# PCB_PI3_v0_1.net
KiCad netlist of a schematic drawn in Altium Designer
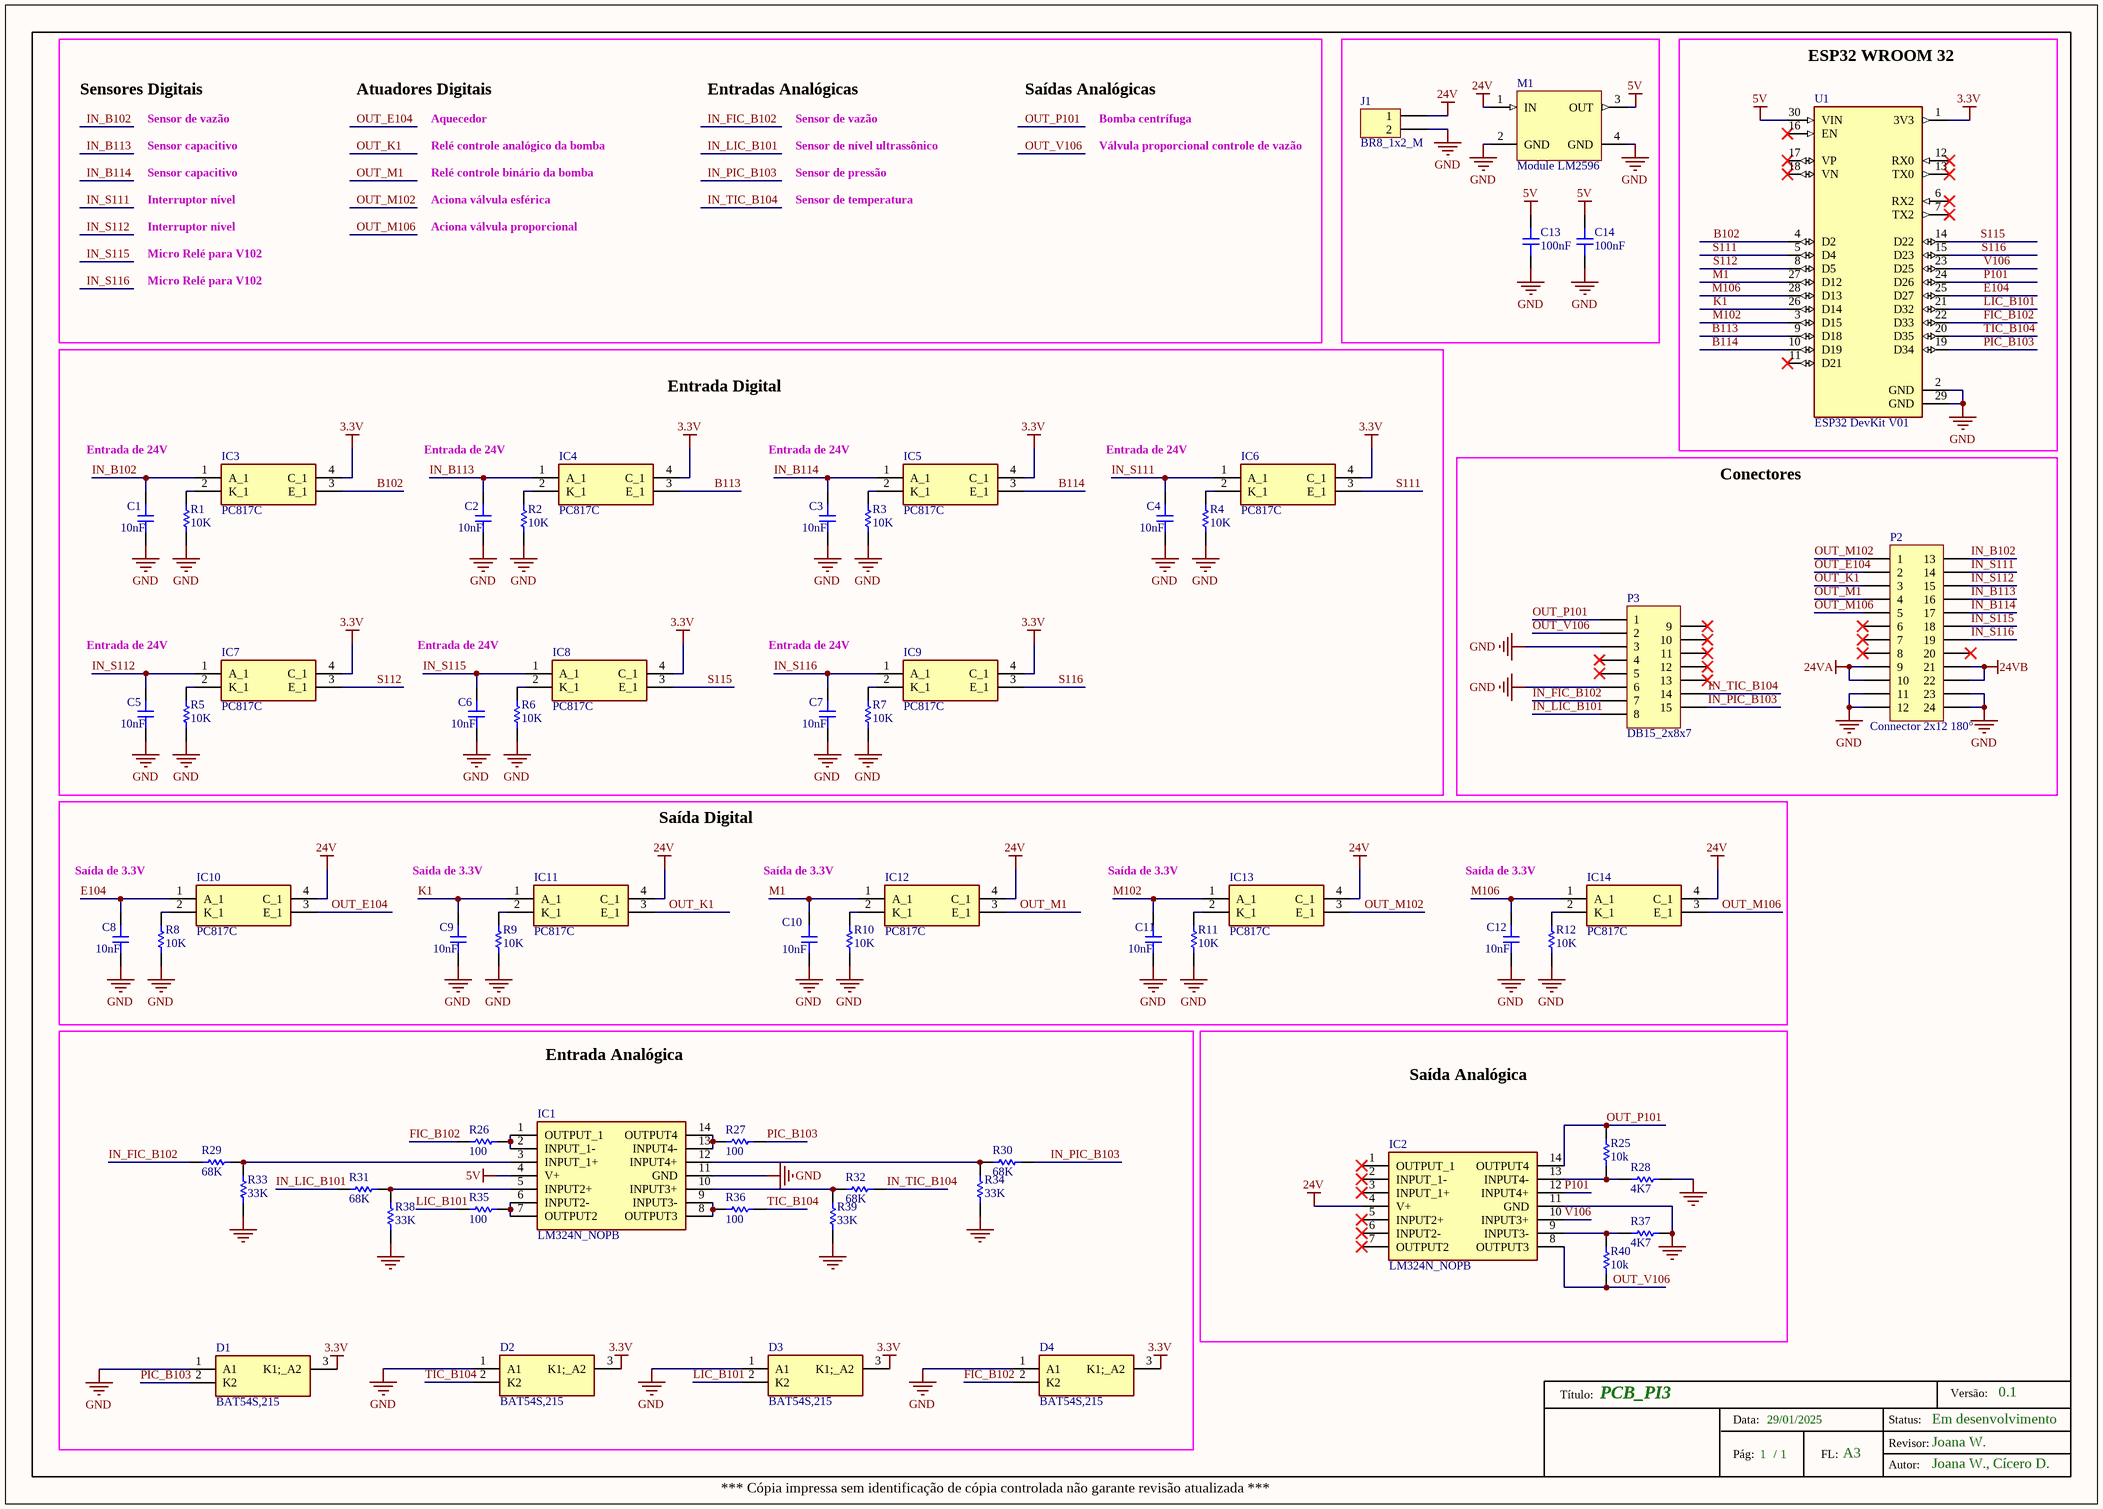
[diagram p0: PCB_PI3_v0.1.SchDoc]

(export (version "E")
  (design (tool "Eeschema 10.0.6"))
  (components
    (comp (ref "C1")
      (value "10nF")
      (footprint "0805C")
      (description "CAP CER 10nF 50V X7R 0805")
      (fields (field (name "VOLTAGE") "50V") (field (name "JLCPCB_PART") "C1710"))
      (libsource (lib "Discrete") (part "C_10nF_0805"))
    )
    (comp (ref "C2")
      (value "10nF")
      (footprint "0805C")
      (description "CAP CER 10nF 50V X7R 0805")
      (fields (field (name "VOLTAGE") "50V") (field (name "JLCPCB_PART") "C1710"))
      (libsource (lib "Discrete") (part "C_10nF_0805"))
    )
    (comp (ref "C3")
      (value "10nF")
      (footprint "0805C")
      (description "CAP CER 10nF 50V X7R 0805")
      (fields (field (name "VOLTAGE") "50V") (field (name "JLCPCB_PART") "C1710"))
      (libsource (lib "Discrete") (part "C_10nF_0805"))
    )
    (comp (ref "C4")
      (value "10nF")
      (footprint "0805C")
      (description "CAP CER 10nF 50V X7R 0805")
      (fields (field (name "VOLTAGE") "50V") (field (name "JLCPCB_PART") "C1710"))
      (libsource (lib "Discrete") (part "C_10nF_0805"))
    )
    (comp (ref "C5")
      (value "10nF")
      (footprint "0805C")
      (description "CAP CER 10nF 50V X7R 0805")
      (fields (field (name "VOLTAGE") "50V") (field (name "JLCPCB_PART") "C1710"))
      (libsource (lib "Discrete") (part "C_10nF_0805"))
    )
    (comp (ref "C6")
      (value "10nF")
      (footprint "0805C")
      (description "CAP CER 10nF 50V X7R 0805")
      (fields (field (name "VOLTAGE") "50V") (field (name "JLCPCB_PART") "C1710"))
      (libsource (lib "Discrete") (part "C_10nF_0805"))
    )
    (comp (ref "C7")
      (value "10nF")
      (footprint "0805C")
      (description "CAP CER 10nF 50V X7R 0805")
      (fields (field (name "VOLTAGE") "50V") (field (name "JLCPCB_PART") "C1710"))
      (libsource (lib "Discrete") (part "C_10nF_0805"))
    )
    (comp (ref "C8")
      (value "10nF")
      (footprint "0805C")
      (description "CAP CER 10nF 50V X7R 0805")
      (fields (field (name "VOLTAGE") "50V") (field (name "JLCPCB_PART") "C1710"))
      (libsource (lib "Discrete") (part "C_10nF_0805"))
    )
    (comp (ref "C9")
      (value "10nF")
      (footprint "0805C")
      (description "CAP CER 10nF 50V X7R 0805")
      (fields (field (name "VOLTAGE") "50V") (field (name "JLCPCB_PART") "C1710"))
      (libsource (lib "Discrete") (part "C_10nF_0805"))
    )
    (comp (ref "C10")
      (value "10nF")
      (footprint "0805C")
      (description "CAP CER 10nF 50V X7R 0805")
      (fields (field (name "VOLTAGE") "50V") (field (name "JLCPCB_PART") "C1710"))
      (libsource (lib "Discrete") (part "C_10nF_0805"))
    )
    (comp (ref "C11")
      (value "10nF")
      (footprint "0805C")
      (description "CAP CER 10nF 50V X7R 0805")
      (fields (field (name "VOLTAGE") "50V") (field (name "JLCPCB_PART") "C1710"))
      (libsource (lib "Discrete") (part "C_10nF_0805"))
    )
    (comp (ref "C12")
      (value "10nF")
      (footprint "0805C")
      (description "CAP CER 10nF 50V X7R 0805")
      (fields (field (name "VOLTAGE") "50V") (field (name "JLCPCB_PART") "C1710"))
      (libsource (lib "Discrete") (part "C_10nF_0805"))
    )
    (comp (ref "C13")
      (value "100nF")
      (footprint "0805C")
      (description "CAP CER 100nF 50V X7R 0805")
      (fields (field (name "VOLTAGE") "50V") (field (name "JLCPCB_PART") "C49678"))
      (libsource (lib "Discrete") (part "C_100nF_0805"))
    )
    (comp (ref "C14")
      (value "100nF")
      (footprint "0805C")
      (description "CAP CER 100nF 50V X7R 0805")
      (fields (field (name "VOLTAGE") "50V") (field (name "JLCPCB_PART") "C49678"))
      (libsource (lib "Discrete") (part "C_100nF_0805"))
    )
    (comp (ref "D1")
      (value "BAT54S,215")
      (footprint "SamacSys:SOT95P230X110-3N")
      (description "Schottky Diode")
      (fields (field (name "MOUSER PART NUMBER") "771-BAT54S-T/R"))
      (libsource (lib "*") (part "BAT54S,215"))
    )
    (comp (ref "D2")
      (value "BAT54S,215")
      (footprint "SamacSys:SOT95P230X110-3N")
      (description "Schottky Diode")
      (fields (field (name "MOUSER PART NUMBER") "771-BAT54S-T/R"))
      (libsource (lib "*") (part "BAT54S,215"))
    )
    (comp (ref "D3")
      (value "BAT54S,215")
      (footprint "SamacSys:SOT95P230X110-3N")
      (description "Schottky Diode")
      (fields (field (name "MOUSER PART NUMBER") "771-BAT54S-T/R"))
      (libsource (lib "*") (part "BAT54S,215"))
    )
    (comp (ref "D4")
      (value "BAT54S,215")
      (footprint "SamacSys:SOT95P230X110-3N")
      (description "Schottky Diode")
      (fields (field (name "MOUSER PART NUMBER") "771-BAT54S-T/R"))
      (libsource (lib "*") (part "BAT54S,215"))
    )
    (comp (ref "IC1")
      (value "LM324N_NOPB")
      (footprint "SamacSys:DIP794W56P254L1905H533Q14N")
      (description "Integrated Circuit")
      (fields
        (field (name "MANUFACTURER_PART_NUMBER") "LM324N/NOPB")
        (field (name "MOUSER PART NUMBER") "926-LM324N/NOPB")
      )
      (libsource (lib "*") (part "LM324N_NOPB"))
    )
    (comp (ref "IC2")
      (value "LM324N_NOPB")
      (footprint "SamacSys:DIP794W56P254L1905H533Q14N")
      (description "Integrated Circuit")
      (fields
        (field (name "MANUFACTURER_PART_NUMBER") "LM324N/NOPB")
        (field (name "MOUSER PART NUMBER") "926-LM324N/NOPB")
      )
      (libsource (lib "*") (part "LM324N_NOPB"))
    )
    (comp (ref "IC3")
      (value "PC817C")
      (footprint "SamacSys:DIP762W60P254L458H450Q4N")
      (description "Integrated Circuit")
      (libsource (lib "SamacSys") (part "PC817C"))
    )
    (comp (ref "IC4")
      (value "PC817C")
      (footprint "SamacSys:DIP762W60P254L458H450Q4N")
      (description "Integrated Circuit")
      (libsource (lib "SamacSys") (part "PC817C"))
    )
    (comp (ref "IC5")
      (value "PC817C")
      (footprint "SamacSys:DIP762W60P254L458H450Q4N")
      (description "Integrated Circuit")
      (libsource (lib "SamacSys") (part "PC817C"))
    )
    (comp (ref "IC6")
      (value "PC817C")
      (footprint "SamacSys:DIP762W60P254L458H450Q4N")
      (description "Integrated Circuit")
      (libsource (lib "SamacSys") (part "PC817C"))
    )
    (comp (ref "IC7")
      (value "PC817C")
      (footprint "SamacSys:DIP762W60P254L458H450Q4N")
      (description "Integrated Circuit")
      (libsource (lib "SamacSys") (part "PC817C"))
    )
    (comp (ref "IC8")
      (value "PC817C")
      (footprint "SamacSys:DIP762W60P254L458H450Q4N")
      (description "Integrated Circuit")
      (libsource (lib "SamacSys") (part "PC817C"))
    )
    (comp (ref "IC9")
      (value "PC817C")
      (footprint "SamacSys:DIP762W60P254L458H450Q4N")
      (description "Integrated Circuit")
      (libsource (lib "SamacSys") (part "PC817C"))
    )
    (comp (ref "IC10")
      (value "PC817C")
      (footprint "SamacSys:DIP762W60P254L458H450Q4N")
      (description "Integrated Circuit")
      (libsource (lib "SamacSys") (part "PC817C"))
    )
    (comp (ref "IC11")
      (value "PC817C")
      (footprint "SamacSys:DIP762W60P254L458H450Q4N")
      (description "Integrated Circuit")
      (libsource (lib "SamacSys") (part "PC817C"))
    )
    (comp (ref "IC12")
      (value "PC817C")
      (footprint "SamacSys:DIP762W60P254L458H450Q4N")
      (description "Integrated Circuit")
      (libsource (lib "SamacSys") (part "PC817C"))
    )
    (comp (ref "IC13")
      (value "PC817C")
      (footprint "SamacSys:DIP762W60P254L458H450Q4N")
      (description "Integrated Circuit")
      (libsource (lib "SamacSys") (part "PC817C"))
    )
    (comp (ref "IC14")
      (value "PC817C")
      (footprint "SamacSys:DIP762W60P254L458H450Q4N")
      (description "Integrated Circuit")
      (libsource (lib "SamacSys") (part "PC817C"))
    )
    (comp (ref "J1")
      (value "BR8_1x2_M")
      (footprint "BR8_1X2_M")
      (description "BR8 Metaltex connector, 1x2, male, 180°")
      (fields (field (name "MANUFACTURER_PART") "BR8MC1-02") (field (name "ML_PART") "CPE08001"))
      (libsource (lib "Connector") (part "BR8_1x2_M"))
    )
    (comp (ref "M1")
      (value "Module LM2596")
      (footprint "MOD_LM2596")
      (description "LM2596 4 Pins")
      (libsource (lib "Module") (part "Mod_Header_LM2596"))
    )
    (comp (ref "P2")
      (value "Connector 2x12 180°")
      (footprint "ds1039")
      (description "Connector DS1078 Female, 180°, 2 Lines, 12 Columns, 24 Pins")
      (libsource (lib "Connector") (part "Connector_2x12_F"))
    )
    (comp (ref "P3")
      (value "DB15_2x8x7")
      (footprint "ds1033")
      (description "Connector DB15 female, 180º, 2 Lines, 7e8 Columns, 26 Pins")
      (libsource (lib "Connector") (part "Connector_2x7e8_F"))
    )
    (comp (ref "R1")
      (value "10K")
      (footprint "0805R")
      (description "RES 10K OHM 5% 1/8W 0805")
      (fields (field (name "JLCPCB_PART") "C17414"))
      (libsource (lib "Discrete") (part "R_10K_0805"))
    )
    (comp (ref "R2")
      (value "10K")
      (footprint "0805R")
      (description "RES 10K OHM 5% 1/8W 0805")
      (fields (field (name "JLCPCB_PART") "C17414"))
      (libsource (lib "Discrete") (part "R_10K_0805"))
    )
    (comp (ref "R3")
      (value "10K")
      (footprint "0805R")
      (description "RES 10K OHM 5% 1/8W 0805")
      (fields (field (name "JLCPCB_PART") "C17414"))
      (libsource (lib "Discrete") (part "R_10K_0805"))
    )
    (comp (ref "R4")
      (value "10K")
      (footprint "0805R")
      (description "RES 10K OHM 5% 1/8W 0805")
      (fields (field (name "JLCPCB_PART") "C17414"))
      (libsource (lib "Discrete") (part "R_10K_0805"))
    )
    (comp (ref "R5")
      (value "10K")
      (footprint "0805R")
      (description "RES 10K OHM 5% 1/8W 0805")
      (fields (field (name "JLCPCB_PART") "C17414"))
      (libsource (lib "Discrete") (part "R_10K_0805"))
    )
    (comp (ref "R6")
      (value "10K")
      (footprint "0805R")
      (description "RES 10K OHM 5% 1/8W 0805")
      (fields (field (name "JLCPCB_PART") "C17414"))
      (libsource (lib "Discrete") (part "R_10K_0805"))
    )
    (comp (ref "R7")
      (value "10K")
      (footprint "0805R")
      (description "RES 10K OHM 5% 1/8W 0805")
      (fields (field (name "JLCPCB_PART") "C17414"))
      (libsource (lib "Discrete") (part "R_10K_0805"))
    )
    (comp (ref "R8")
      (value "10K")
      (footprint "0805R")
      (description "RES 10K OHM 5% 1/8W 0805")
      (fields (field (name "JLCPCB_PART") "C17414"))
      (libsource (lib "Discrete") (part "R_10K_0805"))
    )
    (comp (ref "R9")
      (value "10K")
      (footprint "0805R")
      (description "RES 10K OHM 5% 1/8W 0805")
      (fields (field (name "JLCPCB_PART") "C17414"))
      (libsource (lib "Discrete") (part "R_10K_0805"))
    )
    (comp (ref "R10")
      (value "10K")
      (footprint "0805R")
      (description "RES 10K OHM 5% 1/8W 0805")
      (fields (field (name "JLCPCB_PART") "C17414"))
      (libsource (lib "Discrete") (part "R_10K_0805"))
    )
    (comp (ref "R11")
      (value "10K")
      (footprint "0805R")
      (description "RES 10K OHM 5% 1/8W 0805")
      (fields (field (name "JLCPCB_PART") "C17414"))
      (libsource (lib "Discrete") (part "R_10K_0805"))
    )
    (comp (ref "R12")
      (value "10K")
      (footprint "0805R")
      (description "RES 10K OHM 5% 1/8W 0805")
      (fields (field (name "JLCPCB_PART") "C17414"))
      (libsource (lib "Discrete") (part "R_10K_0805"))
    )
    (comp (ref "R25")
      (value "10k")
      (footprint "RESISTOR")
      (description "RES 10k OHM 5% 1/8W")
      (fields (field (name "JLCPCB_PART") "C17513"))
      (libsource (lib "Discrete") (part "R_10k"))
    )
    (comp (ref "R26")
      (value "100")
      (footprint "RESISTOR")
      (description "RES 100 OHM 5% 1/8")
      (libsource (lib "Discrete") (part "R_0R100"))
    )
    (comp (ref "R27")
      (value "100")
      (footprint "RESISTOR")
      (description "RES 100 OHM 5% 1/8")
      (libsource (lib "Discrete") (part "R_0R100"))
    )
    (comp (ref "R28")
      (value "4K7")
      (footprint "RESISTOR")
      (description "RES 4K7 OHM 5% 1/8W")
      (fields (field (name "JLCPCB_PART") "C17513"))
      (libsource (lib "Discrete") (part "R_4K7"))
    )
    (comp (ref "R29")
      (value "68K")
      (footprint "RESISTOR")
      (description "RES 68K OHM 5% 1/8W")
      (fields (field (name "JLCPCB_PART") "C17513"))
      (libsource (lib "Discrete") (part "R_68K"))
    )
    (comp (ref "R30")
      (value "68K")
      (footprint "RESISTOR")
      (description "RES 68K OHM 5% 1/8W")
      (fields (field (name "JLCPCB_PART") "C17513"))
      (libsource (lib "Discrete") (part "R_68K"))
    )
    (comp (ref "R31")
      (value "68K")
      (footprint "RESISTOR")
      (description "RES 68K OHM 5% 1/8W")
      (fields (field (name "JLCPCB_PART") "C17513"))
      (libsource (lib "Discrete") (part "R_68K"))
    )
    (comp (ref "R32")
      (value "68K")
      (footprint "RESISTOR")
      (description "RES 68K OHM 5% 1/8W")
      (fields (field (name "JLCPCB_PART") "C17513"))
      (libsource (lib "Discrete") (part "R_68K"))
    )
    (comp (ref "R33")
      (value "33K")
      (footprint "RESISTOR")
      (description "RES 33K OHM 5% 1/8W")
      (fields (field (name "JLCPCB_PART") "C17513"))
      (libsource (lib "Discrete") (part "R_33K"))
    )
    (comp (ref "R34")
      (value "33K")
      (footprint "RESISTOR")
      (description "RES 33K OHM 5% 1/8W")
      (fields (field (name "JLCPCB_PART") "C17513"))
      (libsource (lib "Discrete") (part "R_33K"))
    )
    (comp (ref "R35")
      (value "100")
      (footprint "RESISTOR")
      (description "RES 100 OHM 5% 1/8")
      (libsource (lib "Discrete") (part "R_0R100"))
    )
    (comp (ref "R36")
      (value "100")
      (footprint "RESISTOR")
      (description "RES 100 OHM 5% 1/8")
      (libsource (lib "Discrete") (part "R_0R100"))
    )
    (comp (ref "R37")
      (value "4K7")
      (footprint "RESISTOR")
      (description "RES 4K7 OHM 5% 1/8W")
      (fields (field (name "JLCPCB_PART") "C17513"))
      (libsource (lib "Discrete") (part "R_4K7"))
    )
    (comp (ref "R38")
      (value "33K")
      (footprint "RESISTOR")
      (description "RES 33K OHM 5% 1/8W")
      (fields (field (name "JLCPCB_PART") "C17513"))
      (libsource (lib "Discrete") (part "R_33K"))
    )
    (comp (ref "R39")
      (value "33K")
      (footprint "RESISTOR")
      (description "RES 33K OHM 5% 1/8W")
      (fields (field (name "JLCPCB_PART") "C17513"))
      (libsource (lib "Discrete") (part "R_33K"))
    )
    (comp (ref "R40")
      (value "10k")
      (footprint "RESISTOR")
      (description "RES 10k OHM 5% 1/8W")
      (fields (field (name "JLCPCB_PART") "C17513"))
      (libsource (lib "Discrete") (part "R_10k"))
    )
    (comp (ref "U1")
      (value "ESP32 DevKit V01")
      (footprint "ESP32-DEVKIT-V1")
      (description "IC MCU 32BIT ESP32 DEVKIT V01")
      (fields
        (field (name "MANUFACTURER_PART_NUMBER") "ESP-32-DEVKIT-V1")
        (field (name "ML_PART") "CPE11011")
      )
      (libsource (lib "Special") (part "ESP32_DEVKIT"))
    )
  )
  (nets
    (net (code "1") (name "/B102") (class "Default")
      (node (ref "IC3") (pin "3") (pinfunction "E_1_3") (pintype "passive"))
      (node (ref "U1") (pin "4") (pinfunction "D2_4") (pintype "bidirectional"))
    )
    (net (code "2") (name "/B113") (class "Default")
      (node (ref "IC4") (pin "3") (pinfunction "E_1_3") (pintype "passive"))
      (node (ref "U1") (pin "9") (pinfunction "D18_9") (pintype "bidirectional"))
    )
    (net (code "3") (name "/B114") (class "Default")
      (node (ref "IC5") (pin "3") (pinfunction "E_1_3") (pintype "passive"))
      (node (ref "U1") (pin "10") (pinfunction "D19_10") (pintype "bidirectional"))
    )
    (net (code "4") (name "/E104") (class "Default")
      (node (ref "C8") (pin "2") (pinfunction "2_2") (pintype "passive"))
      (node (ref "IC10") (pin "1") (pinfunction "A_1_1") (pintype "passive"))
      (node (ref "U1") (pin "25") (pinfunction "D27_25") (pintype "bidirectional"))
    )
    (net (code "5") (name "/FIC_B102") (class "Default")
      (node (ref "D4") (pin "2") (pinfunction "K2_2") (pintype "passive"))
      (node (ref "R26") (pin "2") (pinfunction "2_2") (pintype "passive"))
      (node (ref "U1") (pin "22") (pinfunction "D33_22") (pintype "bidirectional"))
    )
    (net (code "6") (name "/IN_B102") (class "Default")
      (node (ref "C1") (pin "2") (pinfunction "2_2") (pintype "passive"))
      (node (ref "IC3") (pin "1") (pinfunction "A_1_1") (pintype "passive"))
      (node (ref "P2") (pin "13") (pinfunction "13_13") (pintype "passive"))
    )
    (net (code "7") (name "/IN_B113") (class "Default")
      (node (ref "C2") (pin "2") (pinfunction "2_2") (pintype "passive"))
      (node (ref "IC4") (pin "1") (pinfunction "A_1_1") (pintype "passive"))
      (node (ref "P2") (pin "16") (pinfunction "16_16") (pintype "passive"))
    )
    (net (code "8") (name "/IN_B114") (class "Default")
      (node (ref "C3") (pin "2") (pinfunction "2_2") (pintype "passive"))
      (node (ref "IC5") (pin "1") (pinfunction "A_1_1") (pintype "passive"))
      (node (ref "P2") (pin "17") (pinfunction "17_17") (pintype "passive"))
    )
    (net (code "9") (name "/IN_FIC_B102") (class "Default")
      (node (ref "P3") (pin "7") (pinfunction "7_7") (pintype "passive"))
      (node (ref "R29") (pin "2") (pinfunction "2_2") (pintype "passive"))
    )
    (net (code "10") (name "/IN_LIC_B101") (class "Default")
      (node (ref "P3") (pin "8") (pinfunction "8_8") (pintype "passive"))
      (node (ref "R31") (pin "2") (pinfunction "2_2") (pintype "passive"))
    )
    (net (code "11") (name "/IN_PIC_B103") (class "Default")
      (node (ref "P3") (pin "15") (pinfunction "15_15") (pintype "passive"))
      (node (ref "R30") (pin "1") (pinfunction "1_1") (pintype "passive"))
    )
    (net (code "12") (name "/IN_S111") (class "Default")
      (node (ref "C4") (pin "2") (pinfunction "2_2") (pintype "passive"))
      (node (ref "IC6") (pin "1") (pinfunction "A_1_1") (pintype "passive"))
      (node (ref "P2") (pin "14") (pinfunction "14_14") (pintype "passive"))
    )
    (net (code "13") (name "/IN_S112") (class "Default")
      (node (ref "C5") (pin "2") (pinfunction "2_2") (pintype "passive"))
      (node (ref "IC7") (pin "1") (pinfunction "A_1_1") (pintype "passive"))
      (node (ref "P2") (pin "15") (pinfunction "15_15") (pintype "passive"))
    )
    (net (code "14") (name "/IN_S115") (class "Default")
      (node (ref "C6") (pin "2") (pinfunction "2_2") (pintype "passive"))
      (node (ref "IC8") (pin "1") (pinfunction "A_1_1") (pintype "passive"))
      (node (ref "P2") (pin "18") (pinfunction "18_18") (pintype "passive"))
    )
    (net (code "15") (name "/IN_S116") (class "Default")
      (node (ref "C7") (pin "2") (pinfunction "2_2") (pintype "passive"))
      (node (ref "IC9") (pin "1") (pinfunction "A_1_1") (pintype "passive"))
      (node (ref "P2") (pin "19") (pinfunction "19_19") (pintype "passive"))
    )
    (net (code "16") (name "/IN_TIC_B104") (class "Default")
      (node (ref "P3") (pin "14") (pinfunction "14_14") (pintype "passive"))
      (node (ref "R32") (pin "1") (pinfunction "1_1") (pintype "passive"))
    )
    (net (code "17") (name "/K1") (class "Default")
      (node (ref "C9") (pin "2") (pinfunction "2_2") (pintype "passive"))
      (node (ref "IC11") (pin "1") (pinfunction "A_1_1") (pintype "passive"))
      (node (ref "U1") (pin "26") (pinfunction "D14_26") (pintype "bidirectional"))
    )
    (net (code "18") (name "/LIC_B101") (class "Default")
      (node (ref "D3") (pin "2") (pinfunction "K2_2") (pintype "passive"))
      (node (ref "R35") (pin "2") (pinfunction "2_2") (pintype "passive"))
      (node (ref "U1") (pin "21") (pinfunction "D32_21") (pintype "bidirectional"))
    )
    (net (code "19") (name "/M1") (class "Default")
      (node (ref "C10") (pin "2") (pinfunction "2_2") (pintype "passive"))
      (node (ref "IC12") (pin "1") (pinfunction "A_1_1") (pintype "passive"))
      (node (ref "U1") (pin "27") (pinfunction "D12_27") (pintype "bidirectional"))
    )
    (net (code "20") (name "/M102") (class "Default")
      (node (ref "C11") (pin "2") (pinfunction "2_2") (pintype "passive"))
      (node (ref "IC13") (pin "1") (pinfunction "A_1_1") (pintype "passive"))
      (node (ref "U1") (pin "3") (pinfunction "D15_3") (pintype "bidirectional"))
    )
    (net (code "21") (name "/M106") (class "Default")
      (node (ref "C12") (pin "2") (pinfunction "2_2") (pintype "passive"))
      (node (ref "IC14") (pin "1") (pinfunction "A_1_1") (pintype "passive"))
      (node (ref "U1") (pin "28") (pinfunction "D13_28") (pintype "bidirectional"))
    )
    (net (code "22") (name "/OUT_E104") (class "Default")
      (node (ref "IC10") (pin "3") (pinfunction "E_1_3") (pintype "passive"))
      (node (ref "P2") (pin "2") (pinfunction "2_2") (pintype "passive"))
    )
    (net (code "23") (name "/OUT_K1") (class "Default")
      (node (ref "IC11") (pin "3") (pinfunction "E_1_3") (pintype "passive"))
      (node (ref "P2") (pin "3") (pinfunction "3_3") (pintype "passive"))
    )
    (net (code "24") (name "/OUT_M1") (class "Default")
      (node (ref "IC12") (pin "3") (pinfunction "E_1_3") (pintype "passive"))
      (node (ref "P2") (pin "4") (pinfunction "4_4") (pintype "passive"))
    )
    (net (code "25") (name "/OUT_M102") (class "Default")
      (node (ref "IC13") (pin "3") (pinfunction "E_1_3") (pintype "passive"))
      (node (ref "P2") (pin "1") (pinfunction "1_1") (pintype "passive"))
    )
    (net (code "26") (name "/OUT_M106") (class "Default")
      (node (ref "IC14") (pin "3") (pinfunction "E_1_3") (pintype "passive"))
      (node (ref "P2") (pin "5") (pinfunction "5_5") (pintype "passive"))
    )
    (net (code "27") (name "/OUT_P101") (class "Default")
      (node (ref "IC2") (pin "14") (pinfunction "OUTPUT4_14") (pintype "passive"))
      (node (ref "P3") (pin "1") (pinfunction "1_1") (pintype "passive"))
      (node (ref "R25") (pin "2") (pinfunction "2_2") (pintype "passive"))
    )
    (net (code "28") (name "/OUT_V106") (class "Default")
      (node (ref "IC2") (pin "8") (pinfunction "OUTPUT3_8") (pintype "passive"))
      (node (ref "P3") (pin "2") (pinfunction "2_2") (pintype "passive"))
      (node (ref "R40") (pin "1") (pinfunction "1_1") (pintype "passive"))
    )
    (net (code "29") (name "/P101") (class "Default")
      (node (ref "IC2") (pin "12") (pinfunction "INPUT4+_12") (pintype "passive"))
      (node (ref "U1") (pin "24") (pinfunction "D26_24") (pintype "bidirectional"))
    )
    (net (code "30") (name "/PIC_B103") (class "Default")
      (node (ref "D1") (pin "2") (pinfunction "K2_2") (pintype "passive"))
      (node (ref "R27") (pin "1") (pinfunction "1_1") (pintype "passive"))
      (node (ref "U1") (pin "19") (pinfunction "D34_19") (pintype "bidirectional"))
    )
    (net (code "31") (name "/S111") (class "Default")
      (node (ref "IC6") (pin "3") (pinfunction "E_1_3") (pintype "passive"))
      (node (ref "U1") (pin "5") (pinfunction "D4_5") (pintype "bidirectional"))
    )
    (net (code "32") (name "/S112") (class "Default")
      (node (ref "IC7") (pin "3") (pinfunction "E_1_3") (pintype "passive"))
      (node (ref "U1") (pin "8") (pinfunction "D5_8") (pintype "bidirectional"))
    )
    (net (code "33") (name "/S115") (class "Default")
      (node (ref "IC8") (pin "3") (pinfunction "E_1_3") (pintype "passive"))
      (node (ref "U1") (pin "14") (pinfunction "D22_14") (pintype "bidirectional"))
    )
    (net (code "34") (name "/S116") (class "Default")
      (node (ref "IC9") (pin "3") (pinfunction "E_1_3") (pintype "passive"))
      (node (ref "U1") (pin "15") (pinfunction "D23_15") (pintype "bidirectional"))
    )
    (net (code "35") (name "/TIC_B104") (class "Default")
      (node (ref "D2") (pin "2") (pinfunction "K2_2") (pintype "passive"))
      (node (ref "R36") (pin "1") (pinfunction "1_1") (pintype "passive"))
      (node (ref "U1") (pin "20") (pinfunction "D35_20") (pintype "bidirectional"))
    )
    (net (code "36") (name "/V106") (class "Default")
      (node (ref "IC2") (pin "10") (pinfunction "INPUT3+_10") (pintype "passive"))
      (node (ref "U1") (pin "23") (pinfunction "D25_23") (pintype "bidirectional"))
    )
    (net (code "37") (name "3.3V") (class "Default")
      (node (ref "D1") (pin "3") (pinfunction "K1;_A2_3") (pintype "passive"))
      (node (ref "D2") (pin "3") (pinfunction "K1;_A2_3") (pintype "passive"))
      (node (ref "D3") (pin "3") (pinfunction "K1;_A2_3") (pintype "passive"))
      (node (ref "D4") (pin "3") (pinfunction "K1;_A2_3") (pintype "passive"))
      (node (ref "IC3") (pin "4") (pinfunction "C_1_4") (pintype "passive"))
      (node (ref "IC4") (pin "4") (pinfunction "C_1_4") (pintype "passive"))
      (node (ref "IC5") (pin "4") (pinfunction "C_1_4") (pintype "passive"))
      (node (ref "IC6") (pin "4") (pinfunction "C_1_4") (pintype "passive"))
      (node (ref "IC7") (pin "4") (pinfunction "C_1_4") (pintype "passive"))
      (node (ref "IC8") (pin "4") (pinfunction "C_1_4") (pintype "passive"))
      (node (ref "IC9") (pin "4") (pinfunction "C_1_4") (pintype "passive"))
      (node (ref "U1") (pin "1") (pinfunction "3V3_1") (pintype "output"))
    )
    (net (code "38") (name "5V") (class "Default")
      (node (ref "C13") (pin "2") (pinfunction "2_2") (pintype "passive"))
      (node (ref "C14") (pin "2") (pinfunction "2_2") (pintype "passive"))
      (node (ref "IC1") (pin "4") (pinfunction "V+_4") (pintype "passive"))
      (node (ref "M1") (pin "3") (pinfunction "OUT_3") (pintype "output"))
      (node (ref "U1") (pin "30") (pinfunction "VIN_30") (pintype "input"))
    )
    (net (code "39") (name "24V") (class "Default")
      (node (ref "IC10") (pin "4") (pinfunction "C_1_4") (pintype "passive"))
      (node (ref "IC11") (pin "4") (pinfunction "C_1_4") (pintype "passive"))
      (node (ref "IC12") (pin "4") (pinfunction "C_1_4") (pintype "passive"))
      (node (ref "IC13") (pin "4") (pinfunction "C_1_4") (pintype "passive"))
      (node (ref "IC14") (pin "4") (pinfunction "C_1_4") (pintype "passive"))
      (node (ref "IC2") (pin "4") (pinfunction "V+_4") (pintype "passive"))
      (node (ref "J1") (pin "1") (pinfunction "1_1") (pintype "passive"))
      (node (ref "M1") (pin "1") (pinfunction "IN_1") (pintype "input"))
    )
    (net (code "40") (name "24VA") (class "Default")
      (node (ref "P2") (pin "10") (pinfunction "10_10") (pintype "passive"))
      (node (ref "P2") (pin "9") (pinfunction "9_9") (pintype "passive"))
    )
    (net (code "41") (name "24VB") (class "Default")
      (node (ref "P2") (pin "21") (pinfunction "21_21") (pintype "passive"))
      (node (ref "P2") (pin "22") (pinfunction "22_22") (pintype "passive"))
    )
    (net (code "42") (name "GND") (class "Default")
      (node (ref "C1") (pin "1") (pinfunction "1_1") (pintype "passive"))
      (node (ref "C10") (pin "1") (pinfunction "1_1") (pintype "passive"))
      (node (ref "C11") (pin "1") (pinfunction "1_1") (pintype "passive"))
      (node (ref "C12") (pin "1") (pinfunction "1_1") (pintype "passive"))
      (node (ref "C13") (pin "1") (pinfunction "1_1") (pintype "passive"))
      (node (ref "C14") (pin "1") (pinfunction "1_1") (pintype "passive"))
      (node (ref "C2") (pin "1") (pinfunction "1_1") (pintype "passive"))
      (node (ref "C3") (pin "1") (pinfunction "1_1") (pintype "passive"))
      (node (ref "C4") (pin "1") (pinfunction "1_1") (pintype "passive"))
      (node (ref "C5") (pin "1") (pinfunction "1_1") (pintype "passive"))
      (node (ref "C6") (pin "1") (pinfunction "1_1") (pintype "passive"))
      (node (ref "C7") (pin "1") (pinfunction "1_1") (pintype "passive"))
      (node (ref "C8") (pin "1") (pinfunction "1_1") (pintype "passive"))
      (node (ref "C9") (pin "1") (pinfunction "1_1") (pintype "passive"))
      (node (ref "D1") (pin "1") (pinfunction "A1_1") (pintype "passive"))
      (node (ref "D2") (pin "1") (pinfunction "A1_1") (pintype "passive"))
      (node (ref "D3") (pin "1") (pinfunction "A1_1") (pintype "passive"))
      (node (ref "D4") (pin "1") (pinfunction "A1_1") (pintype "passive"))
      (node (ref "IC1") (pin "11") (pinfunction "GND_11") (pintype "passive"))
      (node (ref "IC2") (pin "11") (pinfunction "GND_11") (pintype "passive"))
      (node (ref "J1") (pin "2") (pinfunction "2_2") (pintype "passive"))
      (node (ref "M1") (pin "2") (pinfunction "GND_2") (pintype "passive"))
      (node (ref "M1") (pin "4") (pinfunction "GND_4") (pintype "passive"))
      (node (ref "P2") (pin "11") (pinfunction "11_11") (pintype "passive"))
      (node (ref "P2") (pin "12") (pinfunction "12_12") (pintype "passive"))
      (node (ref "P2") (pin "23") (pinfunction "23_23") (pintype "passive"))
      (node (ref "P2") (pin "24") (pinfunction "24_24") (pintype "passive"))
      (node (ref "P3") (pin "3") (pinfunction "3_3") (pintype "passive"))
      (node (ref "P3") (pin "6") (pinfunction "6_6") (pintype "passive"))
      (node (ref "R1") (pin "1") (pinfunction "1_1") (pintype "passive"))
      (node (ref "R10") (pin "1") (pinfunction "1_1") (pintype "passive"))
      (node (ref "R11") (pin "1") (pinfunction "1_1") (pintype "passive"))
      (node (ref "R12") (pin "1") (pinfunction "1_1") (pintype "passive"))
      (node (ref "R2") (pin "1") (pinfunction "1_1") (pintype "passive"))
      (node (ref "R28") (pin "1") (pinfunction "1_1") (pintype "passive"))
      (node (ref "R3") (pin "1") (pinfunction "1_1") (pintype "passive"))
      (node (ref "R33") (pin "1") (pinfunction "1_1") (pintype "passive"))
      (node (ref "R34") (pin "1") (pinfunction "1_1") (pintype "passive"))
      (node (ref "R37") (pin "1") (pinfunction "1_1") (pintype "passive"))
      (node (ref "R38") (pin "1") (pinfunction "1_1") (pintype "passive"))
      (node (ref "R39") (pin "1") (pinfunction "1_1") (pintype "passive"))
      (node (ref "R4") (pin "1") (pinfunction "1_1") (pintype "passive"))
      (node (ref "R5") (pin "1") (pinfunction "1_1") (pintype "passive"))
      (node (ref "R6") (pin "1") (pinfunction "1_1") (pintype "passive"))
      (node (ref "R7") (pin "1") (pinfunction "1_1") (pintype "passive"))
      (node (ref "R8") (pin "1") (pinfunction "1_1") (pintype "passive"))
      (node (ref "R9") (pin "1") (pinfunction "1_1") (pintype "passive"))
      (node (ref "U1") (pin "2") (pinfunction "GND_2") (pintype "power_in"))
      (node (ref "U1") (pin "29") (pinfunction "GND_29") (pintype "power_in"))
    )
    (net (code "43") (name "Net-(IC1-INPUT2+)") (class "Default")
      (node (ref "IC1") (pin "5") (pinfunction "INPUT2+_5") (pintype "passive"))
      (node (ref "R31") (pin "1") (pinfunction "1_1") (pintype "passive"))
      (node (ref "R38") (pin "2") (pinfunction "2_2") (pintype "passive"))
    )
    (net (code "44") (name "Net-(IC1-INPUT2-)") (class "Default")
      (node (ref "IC1") (pin "6") (pinfunction "INPUT2-_6") (pintype "passive"))
      (node (ref "IC1") (pin "7") (pinfunction "OUTPUT2_7") (pintype "passive"))
      (node (ref "R35") (pin "1") (pinfunction "1_1") (pintype "passive"))
    )
    (net (code "45") (name "Net-(IC1-INPUT3+)") (class "Default")
      (node (ref "IC1") (pin "10") (pinfunction "INPUT3+_10") (pintype "passive"))
      (node (ref "R32") (pin "2") (pinfunction "2_2") (pintype "passive"))
      (node (ref "R39") (pin "2") (pinfunction "2_2") (pintype "passive"))
    )
    (net (code "46") (name "Net-(IC1-INPUT3-)") (class "Default")
      (node (ref "IC1") (pin "8") (pinfunction "OUTPUT3_8") (pintype "passive"))
      (node (ref "IC1") (pin "9") (pinfunction "INPUT3-_9") (pintype "passive"))
      (node (ref "R36") (pin "2") (pinfunction "2_2") (pintype "passive"))
    )
    (net (code "47") (name "Net-(IC1-INPUT4+)") (class "Default")
      (node (ref "IC1") (pin "12") (pinfunction "INPUT4+_12") (pintype "passive"))
      (node (ref "R30") (pin "2") (pinfunction "2_2") (pintype "passive"))
      (node (ref "R34") (pin "2") (pinfunction "2_2") (pintype "passive"))
    )
    (net (code "48") (name "Net-(IC1-INPUT4-)") (class "Default")
      (node (ref "IC1") (pin "13") (pinfunction "INPUT4-_13") (pintype "passive"))
      (node (ref "IC1") (pin "14") (pinfunction "OUTPUT4_14") (pintype "passive"))
      (node (ref "R27") (pin "2") (pinfunction "2_2") (pintype "passive"))
    )
    (net (code "49") (name "Net-(IC1-INPUT_1+)") (class "Default")
      (node (ref "IC1") (pin "3") (pinfunction "INPUT_1+_3") (pintype "passive"))
      (node (ref "R29") (pin "1") (pinfunction "1_1") (pintype "passive"))
      (node (ref "R33") (pin "2") (pinfunction "2_2") (pintype "passive"))
    )
    (net (code "50") (name "Net-(IC1-INPUT_1-)") (class "Default")
      (node (ref "IC1") (pin "1") (pinfunction "OUTPUT_1_1") (pintype "passive"))
      (node (ref "IC1") (pin "2") (pinfunction "INPUT_1-_2") (pintype "passive"))
      (node (ref "R26") (pin "1") (pinfunction "1_1") (pintype "passive"))
    )
    (net (code "51") (name "Net-(IC2-INPUT3-)") (class "Default")
      (node (ref "IC2") (pin "9") (pinfunction "INPUT3-_9") (pintype "passive"))
      (node (ref "R37") (pin "2") (pinfunction "2_2") (pintype "passive"))
      (node (ref "R40") (pin "2") (pinfunction "2_2") (pintype "passive"))
    )
    (net (code "52") (name "Net-(IC2-INPUT4-)") (class "Default")
      (node (ref "IC2") (pin "13") (pinfunction "INPUT4-_13") (pintype "passive"))
      (node (ref "R25") (pin "1") (pinfunction "1_1") (pintype "passive"))
      (node (ref "R28") (pin "2") (pinfunction "2_2") (pintype "passive"))
    )
    (net (code "53") (name "Net-(IC3-K_1)") (class "Default")
      (node (ref "IC3") (pin "2") (pinfunction "K_1_2") (pintype "passive"))
      (node (ref "R1") (pin "2") (pinfunction "2_2") (pintype "passive"))
    )
    (net (code "54") (name "Net-(IC4-K_1)") (class "Default")
      (node (ref "IC4") (pin "2") (pinfunction "K_1_2") (pintype "passive"))
      (node (ref "R2") (pin "2") (pinfunction "2_2") (pintype "passive"))
    )
    (net (code "55") (name "Net-(IC5-K_1)") (class "Default")
      (node (ref "IC5") (pin "2") (pinfunction "K_1_2") (pintype "passive"))
      (node (ref "R3") (pin "2") (pinfunction "2_2") (pintype "passive"))
    )
    (net (code "56") (name "Net-(IC6-K_1)") (class "Default")
      (node (ref "IC6") (pin "2") (pinfunction "K_1_2") (pintype "passive"))
      (node (ref "R4") (pin "2") (pinfunction "2_2") (pintype "passive"))
    )
    (net (code "57") (name "Net-(IC7-K_1)") (class "Default")
      (node (ref "IC7") (pin "2") (pinfunction "K_1_2") (pintype "passive"))
      (node (ref "R5") (pin "2") (pinfunction "2_2") (pintype "passive"))
    )
    (net (code "58") (name "Net-(IC8-K_1)") (class "Default")
      (node (ref "IC8") (pin "2") (pinfunction "K_1_2") (pintype "passive"))
      (node (ref "R6") (pin "2") (pinfunction "2_2") (pintype "passive"))
    )
    (net (code "59") (name "Net-(IC9-K_1)") (class "Default")
      (node (ref "IC9") (pin "2") (pinfunction "K_1_2") (pintype "passive"))
      (node (ref "R7") (pin "2") (pinfunction "2_2") (pintype "passive"))
    )
    (net (code "60") (name "Net-(IC10-K_1)") (class "Default")
      (node (ref "IC10") (pin "2") (pinfunction "K_1_2") (pintype "passive"))
      (node (ref "R8") (pin "2") (pinfunction "2_2") (pintype "passive"))
    )
    (net (code "61") (name "Net-(IC11-K_1)") (class "Default")
      (node (ref "IC11") (pin "2") (pinfunction "K_1_2") (pintype "passive"))
      (node (ref "R9") (pin "2") (pinfunction "2_2") (pintype "passive"))
    )
    (net (code "62") (name "Net-(IC12-K_1)") (class "Default")
      (node (ref "IC12") (pin "2") (pinfunction "K_1_2") (pintype "passive"))
      (node (ref "R10") (pin "2") (pinfunction "2_2") (pintype "passive"))
    )
    (net (code "63") (name "Net-(IC13-K_1)") (class "Default")
      (node (ref "IC13") (pin "2") (pinfunction "K_1_2") (pintype "passive"))
      (node (ref "R11") (pin "2") (pinfunction "2_2") (pintype "passive"))
    )
    (net (code "64") (name "Net-(IC14-K_1)") (class "Default")
      (node (ref "IC14") (pin "2") (pinfunction "K_1_2") (pintype "passive"))
      (node (ref "R12") (pin "2") (pinfunction "2_2") (pintype "passive"))
    )
    (net (code "65") (name "unconnected-(IC2-INPUT2+-Pad5)") (class "Default")
      (node (ref "IC2") (pin "5") (pinfunction "INPUT2+_5") (pintype "passive+no_connect"))
    )
    (net (code "66") (name "unconnected-(IC2-INPUT2--Pad6)") (class "Default")
      (node (ref "IC2") (pin "6") (pinfunction "INPUT2-_6") (pintype "passive+no_connect"))
    )
    (net (code "67") (name "unconnected-(IC2-INPUT_1+-Pad3)") (class "Default")
      (node (ref "IC2") (pin "3") (pinfunction "INPUT_1+_3") (pintype "passive+no_connect"))
    )
    (net (code "68") (name "unconnected-(IC2-INPUT_1--Pad2)") (class "Default")
      (node (ref "IC2") (pin "2") (pinfunction "INPUT_1-_2") (pintype "passive+no_connect"))
    )
    (net (code "69") (name "unconnected-(IC2-OUTPUT2-Pad7)") (class "Default")
      (node (ref "IC2") (pin "7") (pinfunction "OUTPUT2_7") (pintype "passive+no_connect"))
    )
    (net (code "70") (name "unconnected-(IC2-OUTPUT_1-Pad1)") (class "Default")
      (node (ref "IC2") (pin "1") (pinfunction "OUTPUT_1_1") (pintype "passive+no_connect"))
    )
    (net (code "71") (name "unconnected-(P2-Pad6)") (class "Default")
      (node (ref "P2") (pin "6") (pinfunction "6_6") (pintype "passive+no_connect"))
    )
    (net (code "72") (name "unconnected-(P2-Pad7)") (class "Default")
      (node (ref "P2") (pin "7") (pinfunction "7_7") (pintype "passive+no_connect"))
    )
    (net (code "73") (name "unconnected-(P2-Pad8)") (class "Default")
      (node (ref "P2") (pin "8") (pinfunction "8_8") (pintype "passive+no_connect"))
    )
    (net (code "74") (name "unconnected-(P2-Pad20)") (class "Default")
      (node (ref "P2") (pin "20") (pinfunction "20_20") (pintype "passive+no_connect"))
    )
    (net (code "75") (name "unconnected-(P3-Pad4)") (class "Default")
      (node (ref "P3") (pin "4") (pinfunction "4_4") (pintype "passive+no_connect"))
    )
    (net (code "76") (name "unconnected-(P3-Pad5)") (class "Default")
      (node (ref "P3") (pin "5") (pinfunction "5_5") (pintype "passive+no_connect"))
    )
    (net (code "77") (name "unconnected-(P3-Pad9)") (class "Default")
      (node (ref "P3") (pin "9") (pinfunction "9_9") (pintype "passive+no_connect"))
    )
    (net (code "78") (name "unconnected-(P3-Pad10)") (class "Default")
      (node (ref "P3") (pin "10") (pinfunction "10_10") (pintype "passive+no_connect"))
    )
    (net (code "79") (name "unconnected-(P3-Pad11)") (class "Default")
      (node (ref "P3") (pin "11") (pinfunction "11_11") (pintype "passive+no_connect"))
    )
    (net (code "80") (name "unconnected-(P3-Pad12)") (class "Default")
      (node (ref "P3") (pin "12") (pinfunction "12_12") (pintype "passive+no_connect"))
    )
    (net (code "81") (name "unconnected-(P3-Pad13)") (class "Default")
      (node (ref "P3") (pin "13") (pinfunction "13_13") (pintype "passive+no_connect"))
    )
    (net (code "82") (name "unconnected-(U1-D21-Pad11)") (class "Default")
      (node (ref "U1") (pin "11") (pinfunction "D21_11") (pintype "bidirectional+no_connect"))
    )
    (net (code "83") (name "unconnected-(U1-EN-Pad16)") (class "Default")
      (node (ref "U1") (pin "16") (pinfunction "EN_16") (pintype "input+no_connect"))
    )
    (net (code "84") (name "unconnected-(U1-RX0-Pad12)") (class "Default")
      (node (ref "U1") (pin "12") (pinfunction "RX0_12") (pintype "input+no_connect"))
    )
    (net (code "85") (name "unconnected-(U1-RX2-Pad6)") (class "Default")
      (node (ref "U1") (pin "6") (pinfunction "RX2_6") (pintype "input+no_connect"))
    )
    (net (code "86") (name "unconnected-(U1-TX0-Pad13)") (class "Default")
      (node (ref "U1") (pin "13") (pinfunction "TX0_13") (pintype "output+no_connect"))
    )
    (net (code "87") (name "unconnected-(U1-TX2-Pad7)") (class "Default")
      (node (ref "U1") (pin "7") (pinfunction "TX2_7") (pintype "output+no_connect"))
    )
    (net (code "88") (name "unconnected-(U1-VN-Pad18)") (class "Default")
      (node (ref "U1") (pin "18") (pinfunction "VN_18") (pintype "bidirectional+no_connect"))
    )
    (net (code "89") (name "unconnected-(U1-VP-Pad17)") (class "Default")
      (node (ref "U1") (pin "17") (pinfunction "VP_17") (pintype "bidirectional+no_connect"))
    )
  )
)
